# RFRxTx_2550_a.net
KiCad netlist of a schematic drawn in EAGLE
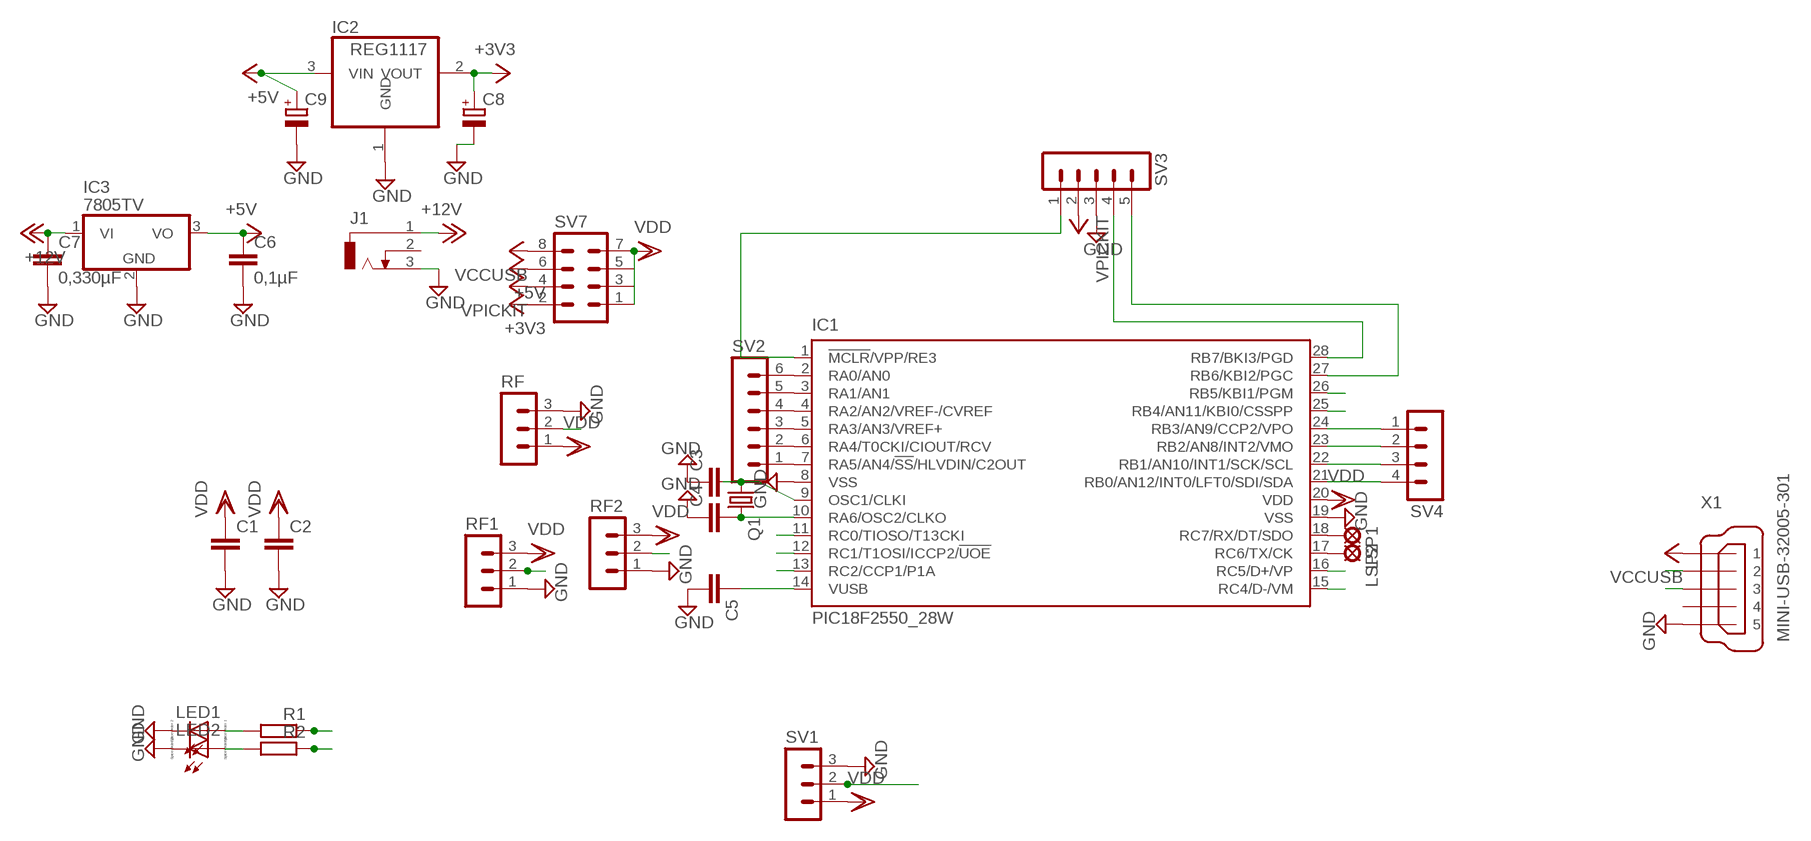
[diagram p0: schematic, sheet 1]

(export (version "E")
  (design (tool "Eeschema 10.0.6"))
  (components
    (comp (ref "C1")
      (value "C-EUC0805")
      (footprint "eagle-import:C0805")
      (libsource (lib "eagle-import") (part "C-EUC0805"))
    )
    (comp (ref "C2")
      (value "C-EUC0805")
      (footprint "eagle-import:C0805")
      (libsource (lib "eagle-import") (part "C-EUC0805"))
    )
    (comp (ref "C3")
      (value "C-EUC0805")
      (footprint "eagle-import:C0805")
      (libsource (lib "eagle-import") (part "C-EUC0805"))
    )
    (comp (ref "C4")
      (value "C-EUC0805")
      (footprint "eagle-import:C0805")
      (libsource (lib "eagle-import") (part "C-EUC0805"))
    )
    (comp (ref "C5")
      (value "C-EUC0805")
      (footprint "eagle-import:C0805")
      (libsource (lib "eagle-import") (part "C-EUC0805"))
    )
    (comp (ref "C6")
      (value "0,1µF")
      (footprint "eagle-import:C0805")
      (libsource (lib "eagle-import") (part "resistor_C-EUC0805"))
    )
    (comp (ref "C7")
      (value "0,330µF")
      (footprint "eagle-import:C0805")
      (libsource (lib "eagle-import") (part "resistor_C-EUC0805"))
    )
    (comp (ref "C8")
      (value "CPOL-EU153CLV-0405")
      (footprint "eagle-import:153CLV-0405")
      (libsource (lib "eagle-import") (part "CPOL-EU153CLV-0405"))
    )
    (comp (ref "C9")
      (value "CPOL-EU153CLV-0405")
      (footprint "eagle-import:153CLV-0405")
      (libsource (lib "eagle-import") (part "CPOL-EU153CLV-0405"))
    )
    (comp (ref "IC1")
      (value "PIC18F2550_28W")
      (footprint "eagle-import:SO28W")
      (fields (field (name "MF") "MICROCHIP") (field (name "MPN") "PIC18F2550-I/SO"))
      (libsource (lib "eagle-import") (part "PIC18F2_28W550"))
    )
    (comp (ref "IC2")
      (value "REG1117")
      (footprint "eagle-import:SOT223")
      (libsource (lib "eagle-import") (part "REG1117"))
    )
    (comp (ref "IC3")
      (value "7805TV")
      (footprint "eagle-import:TO220V")
      (libsource (lib "eagle-import") (part "78TV05"))
    )
    (comp (ref "J1")
      (value "DCJ0303")
      (footprint "eagle-import:DCJ0303")
      (libsource (lib "eagle-import") (part "DCJ0303"))
    )
    (comp (ref "LED1")
      (value "LED_ESML0603")
      (footprint "eagle-import:LED_SML0603")
      (libsource (lib "eagle-import") (part "LED_ESML0603"))
    )
    (comp (ref "LED2")
      (value "LED_ESML0603")
      (footprint "eagle-import:LED_SML0603")
      (libsource (lib "eagle-import") (part "LED_ESML0603"))
    )
    (comp (ref "LSP1")
      (value "LSP10")
      (footprint "eagle-import:LSP10")
      (libsource (lib "eagle-import") (part "LSP10"))
    )
    (comp (ref "LSP2")
      (value "LSP10")
      (footprint "eagle-import:LSP10")
      (libsource (lib "eagle-import") (part "LSP10"))
    )
    (comp (ref "Q1")
      (value "CRYSTALSM49")
      (footprint "eagle-import:SM49")
      (libsource (lib "eagle-import") (part "CRYSTALSM49"))
    )
    (comp (ref "R1")
      (value "R-EU_R0805")
      (footprint "eagle-import:R0805")
      (libsource (lib "eagle-import") (part "R-EU_R0805"))
    )
    (comp (ref "R2")
      (value "R-EU_R0805")
      (footprint "eagle-import:R0805")
      (libsource (lib "eagle-import") (part "R-EU_R0805"))
    )
    (comp (ref "RF")
      (value "MA03-1")
      (footprint "eagle-import:MA03-1")
      (libsource (lib "eagle-import") (part "MA03-1"))
    )
    (comp (ref "RF1")
      (value "MA03-1")
      (footprint "eagle-import:MA03-1")
      (libsource (lib "eagle-import") (part "MA03-1"))
    )
    (comp (ref "RF2")
      (value "MA03-1")
      (footprint "eagle-import:MA03-1")
      (libsource (lib "eagle-import") (part "MA03-1"))
    )
    (comp (ref "SV1")
      (value "MA03-1")
      (footprint "eagle-import:MA03-1")
      (libsource (lib "eagle-import") (part "MA03-1"))
    )
    (comp (ref "SV2")
      (value "MA06-1")
      (footprint "eagle-import:MA06-1")
      (libsource (lib "eagle-import") (part "MA06-1"))
    )
    (comp (ref "SV3")
      (value "MA05-1")
      (footprint "eagle-import:MA05-1")
      (libsource (lib "eagle-import") (part "MA05-1"))
    )
    (comp (ref "SV4")
      (value "MA04-1")
      (footprint "eagle-import:MA04-1")
      (libsource (lib "eagle-import") (part "MA04-1"))
    )
    (comp (ref "SV7")
      (value "MA04-2")
      (footprint "eagle-import:MA04-2")
      (libsource (lib "eagle-import") (part "MA04-2"))
    )
    (comp (ref "X1")
      (value "MINI-USB-32005-301")
      (footprint "eagle-import:32005-301")
      (libsource (lib "eagle-import") (part "MINI-USB-32005-301"))
    )
  )
  (nets
    (net (code "1") (name "+3V3") (class "Default")
      (node (ref "C8") (pin "+") (pinfunction "+_+") (pintype "passive"))
      (node (ref "IC2") (pin "2") (pinfunction "VOUT_2") (pintype "output"))
      (node (ref "SV7") (pin "2") (pinfunction "2_2") (pintype "passive"))
    )
    (net (code "2") (name "+5V") (class "Default")
      (node (ref "C6") (pin "1") (pinfunction "1_1") (pintype "passive"))
      (node (ref "C9") (pin "+") (pinfunction "+_+") (pintype "passive"))
      (node (ref "IC2") (pin "3") (pinfunction "VIN_3") (pintype "input"))
      (node (ref "IC3") (pin "3") (pinfunction "VO_3") (pintype "passive"))
      (node (ref "SV7") (pin "6") (pinfunction "6_6") (pintype "passive"))
    )
    (net (code "3") (name "+12V") (class "Default")
      (node (ref "C7") (pin "1") (pinfunction "1_1") (pintype "passive"))
      (node (ref "IC3") (pin "1") (pinfunction "VI_1") (pintype "input"))
      (node (ref "J1") (pin "1") (pinfunction "1_1") (pintype "passive"))
    )
    (net (code "4") (name "/CCP2") (class "Default")
      (node (ref "IC1") (pin "24") (pinfunction "RB3/AN9/CCP2/VPO_24") (pintype "bidirectional"))
      (node (ref "SV1") (pin "2") (pinfunction "2_2") (pintype "passive"))
      (node (ref "SV4") (pin "1") (pinfunction "1_1") (pintype "passive"))
    )
    (net (code "5") (name "/D+") (class "Default")
      (node (ref "IC1") (pin "16") (pinfunction "RC5/D+/VP_16") (pintype "bidirectional"))
      (node (ref "X1") (pin "3") (pinfunction "3_3") (pintype "passive"))
    )
    (net (code "6") (name "/D-") (class "Default")
      (node (ref "IC1") (pin "15") (pinfunction "RC4/D-/VM_15") (pintype "bidirectional"))
      (node (ref "X1") (pin "2") (pinfunction "2_2") (pintype "passive"))
    )
    (net (code "7") (name "/IR") (class "Default")
      (node (ref "IC1") (pin "13") (pinfunction "RC2/CCP1/P1A_13") (pintype "bidirectional"))
      (node (ref "RF1") (pin "2") (pinfunction "2_2") (pintype "passive"))
    )
    (net (code "8") (name "/RB4") (class "Default")
      (node (ref "IC1") (pin "25") (pinfunction "RB4/AN11/KBI0/CSSPP_25") (pintype "bidirectional"))
      (node (ref "R2") (pin "1") (pinfunction "1_1") (pintype "passive"))
    )
    (net (code "9") (name "/RB5") (class "Default")
      (node (ref "IC1") (pin "26") (pinfunction "RB5/KBI1/PGM_26") (pintype "bidirectional"))
      (node (ref "R1") (pin "1") (pinfunction "1_1") (pintype "passive"))
    )
    (net (code "10") (name "/RC0") (class "Default")
      (node (ref "IC1") (pin "11") (pinfunction "RC0/TIOSO/T13CKI_11") (pintype "bidirectional"))
      (node (ref "RF2") (pin "2") (pinfunction "2_2") (pintype "passive"))
    )
    (net (code "11") (name "/RF") (class "Default")
      (node (ref "IC1") (pin "12") (pinfunction "RC1/T1OSI/ICCP2/~{UOE}_12") (pintype "bidirectional"))
      (node (ref "RF") (pin "2") (pinfunction "2_2") (pintype "passive"))
    )
    (net (code "12") (name "GND") (class "Default")
      (node (ref "C1") (pin "2") (pinfunction "2_2") (pintype "passive"))
      (node (ref "C2") (pin "2") (pinfunction "2_2") (pintype "passive"))
      (node (ref "C3") (pin "1") (pinfunction "1_1") (pintype "passive"))
      (node (ref "C4") (pin "1") (pinfunction "1_1") (pintype "passive"))
      (node (ref "C5") (pin "2") (pinfunction "2_2") (pintype "passive"))
      (node (ref "C6") (pin "2") (pinfunction "2_2") (pintype "passive"))
      (node (ref "C7") (pin "2") (pinfunction "2_2") (pintype "passive"))
      (node (ref "C8") (pin "-") (pinfunction "-_-") (pintype "passive"))
      (node (ref "C9") (pin "-") (pinfunction "-_-") (pintype "passive"))
      (node (ref "IC1") (pin "19") (pinfunction "VSS_19") (pintype "power_in"))
      (node (ref "IC1") (pin "8") (pinfunction "VSS_8") (pintype "power_in"))
      (node (ref "IC2") (pin "1") (pinfunction "GND_1") (pintype "power_in"))
      (node (ref "IC3") (pin "2") (pinfunction "GND_2") (pintype "passive"))
      (node (ref "J1") (pin "3") (pinfunction "3_3") (pintype "passive"))
      (node (ref "LED1") (pin "C") (pinfunction "C_C") (pintype "passive"))
      (node (ref "LED2") (pin "C") (pinfunction "C_C") (pintype "passive"))
      (node (ref "RF") (pin "3") (pinfunction "3_3") (pintype "passive"))
      (node (ref "RF1") (pin "1") (pinfunction "1_1") (pintype "passive"))
      (node (ref "RF2") (pin "1") (pinfunction "1_1") (pintype "passive"))
      (node (ref "SV1") (pin "3") (pinfunction "3_3") (pintype "passive"))
      (node (ref "SV3") (pin "3") (pinfunction "3_3") (pintype "passive"))
      (node (ref "X1") (pin "5") (pinfunction "5_5") (pintype "passive"))
    )
    (net (code "13") (name "Net-(IC1-OSC1{slash}CLKI)") (class "Default")
      (node (ref "C3") (pin "2") (pinfunction "2_2") (pintype "passive"))
      (node (ref "IC1") (pin "9") (pinfunction "OSC1/CLKI_9") (pintype "input"))
      (node (ref "Q1") (pin "1") (pinfunction "1_1") (pintype "passive"))
    )
    (net (code "14") (name "Net-(IC1-RA0{slash}AN0)") (class "Default")
      (node (ref "IC1") (pin "2") (pinfunction "RA0/AN0_2") (pintype "bidirectional"))
      (node (ref "SV2") (pin "6") (pinfunction "6_6") (pintype "passive"))
    )
    (net (code "15") (name "Net-(IC1-RA1{slash}AN1)") (class "Default")
      (node (ref "IC1") (pin "3") (pinfunction "RA1/AN1_3") (pintype "bidirectional"))
      (node (ref "SV2") (pin "5") (pinfunction "5_5") (pintype "passive"))
    )
    (net (code "16") (name "Net-(IC1-RA2{slash}AN2{slash}VREF-{slash}CVREF)") (class "Default")
      (node (ref "IC1") (pin "4") (pinfunction "RA2/AN2/VREF-/CVREF_4") (pintype "bidirectional"))
      (node (ref "SV2") (pin "4") (pinfunction "4_4") (pintype "passive"))
    )
    (net (code "17") (name "Net-(IC1-RA3{slash}AN3{slash}VREF+)") (class "Default")
      (node (ref "IC1") (pin "5") (pinfunction "RA3/AN3/VREF+_5") (pintype "bidirectional"))
      (node (ref "SV2") (pin "3") (pinfunction "3_3") (pintype "passive"))
    )
    (net (code "18") (name "Net-(IC1-RA4{slash}T0CKI{slash}CIOUT{slash}RCV)") (class "Default")
      (node (ref "IC1") (pin "6") (pinfunction "RA4/T0CKI/CIOUT/RCV_6") (pintype "bidirectional"))
      (node (ref "SV2") (pin "2") (pinfunction "2_2") (pintype "passive"))
    )
    (net (code "19") (name "Net-(IC1-RA5{slash}AN4{slash}~{SS}{slash}HLVDIN{slash}C2OUT)") (class "Default")
      (node (ref "IC1") (pin "7") (pinfunction "RA5/AN4/~{SS}/HLVDIN/C2OUT_7") (pintype "bidirectional"))
      (node (ref "SV2") (pin "1") (pinfunction "1_1") (pintype "passive"))
    )
    (net (code "20") (name "Net-(IC1-RA6{slash}OSC2{slash}CLKO)") (class "Default")
      (node (ref "C4") (pin "2") (pinfunction "2_2") (pintype "passive"))
      (node (ref "IC1") (pin "10") (pinfunction "RA6/OSC2/CLKO_10") (pintype "output"))
      (node (ref "Q1") (pin "2") (pinfunction "2_2") (pintype "passive"))
    )
    (net (code "21") (name "Net-(IC1-RB0{slash}AN12{slash}INT0{slash}LFT0{slash}SDI{slash}SDA)") (class "Default")
      (node (ref "IC1") (pin "21") (pinfunction "RB0/AN12/INT0/LFT0/SDI/SDA_21") (pintype "bidirectional"))
      (node (ref "SV4") (pin "4") (pinfunction "4_4") (pintype "passive"))
    )
    (net (code "22") (name "Net-(IC1-RB1{slash}AN10{slash}INT1{slash}SCK{slash}SCL)") (class "Default")
      (node (ref "IC1") (pin "22") (pinfunction "RB1/AN10/INT1/SCK/SCL_22") (pintype "bidirectional"))
      (node (ref "SV4") (pin "3") (pinfunction "3_3") (pintype "passive"))
    )
    (net (code "23") (name "Net-(IC1-RB2{slash}AN8{slash}INT2{slash}VMO)") (class "Default")
      (node (ref "IC1") (pin "23") (pinfunction "RB2/AN8/INT2/VMO_23") (pintype "bidirectional"))
      (node (ref "SV4") (pin "2") (pinfunction "2_2") (pintype "passive"))
    )
    (net (code "24") (name "Net-(IC1-RB6{slash}KBI2{slash}PGC)") (class "Default")
      (node (ref "IC1") (pin "27") (pinfunction "RB6/KBI2/PGC_27") (pintype "bidirectional"))
      (node (ref "SV3") (pin "5") (pinfunction "5_5") (pintype "passive"))
    )
    (net (code "25") (name "Net-(IC1-RB7{slash}BKI3{slash}PGD)") (class "Default")
      (node (ref "IC1") (pin "28") (pinfunction "RB7/BKI3/PGD_28") (pintype "bidirectional"))
      (node (ref "SV3") (pin "4") (pinfunction "4_4") (pintype "passive"))
    )
    (net (code "26") (name "Net-(IC1-RC6{slash}TX{slash}CK)") (class "Default")
      (node (ref "IC1") (pin "17") (pinfunction "RC6/TX/CK_17") (pintype "bidirectional"))
      (node (ref "LSP2") (pin "MP") (pinfunction "MP_MP") (pintype "passive"))
    )
    (net (code "27") (name "Net-(IC1-RC7{slash}RX{slash}DT{slash}SDO)") (class "Default")
      (node (ref "IC1") (pin "18") (pinfunction "RC7/RX/DT/SDO_18") (pintype "bidirectional"))
      (node (ref "LSP1") (pin "MP") (pinfunction "MP_MP") (pintype "passive"))
    )
    (net (code "28") (name "Net-(IC1-VUSB)") (class "Default")
      (node (ref "C5") (pin "1") (pinfunction "1_1") (pintype "passive"))
      (node (ref "IC1") (pin "14") (pinfunction "VUSB_14") (pintype "bidirectional"))
    )
    (net (code "29") (name "Net-(IC1-~{MCLR}{slash}VPP{slash}RE3)") (class "Default")
      (node (ref "IC1") (pin "1") (pinfunction "~{MCLR}/VPP/RE3_1") (pintype "input"))
      (node (ref "SV3") (pin "1") (pinfunction "1_1") (pintype "passive"))
    )
    (net (code "30") (name "Net-(LED1-PadA)") (class "Default")
      (node (ref "LED1") (pin "A") (pinfunction "A_A") (pintype "passive"))
      (node (ref "R1") (pin "2") (pinfunction "2_2") (pintype "passive"))
    )
    (net (code "31") (name "Net-(LED2-PadA)") (class "Default")
      (node (ref "LED2") (pin "A") (pinfunction "A_A") (pintype "passive"))
      (node (ref "R2") (pin "2") (pinfunction "2_2") (pintype "passive"))
    )
    (net (code "32") (name "VCCUSB") (class "Default")
      (node (ref "SV7") (pin "8") (pinfunction "8_8") (pintype "passive"))
      (node (ref "X1") (pin "1") (pinfunction "1_1") (pintype "passive"))
    )
    (net (code "33") (name "VDD") (class "Default")
      (node (ref "C1") (pin "1") (pinfunction "1_1") (pintype "passive"))
      (node (ref "C2") (pin "1") (pinfunction "1_1") (pintype "passive"))
      (node (ref "IC1") (pin "20") (pinfunction "VDD_20") (pintype "power_in"))
      (node (ref "RF") (pin "1") (pinfunction "1_1") (pintype "passive"))
      (node (ref "RF1") (pin "3") (pinfunction "3_3") (pintype "passive"))
      (node (ref "RF2") (pin "3") (pinfunction "3_3") (pintype "passive"))
      (node (ref "SV1") (pin "1") (pinfunction "1_1") (pintype "passive"))
      (node (ref "SV7") (pin "1") (pinfunction "1_1") (pintype "passive"))
      (node (ref "SV7") (pin "3") (pinfunction "3_3") (pintype "passive"))
      (node (ref "SV7") (pin "5") (pinfunction "5_5") (pintype "passive"))
      (node (ref "SV7") (pin "7") (pinfunction "7_7") (pintype "passive"))
    )
    (net (code "34") (name "VPICKIT") (class "Default")
      (node (ref "SV3") (pin "2") (pinfunction "2_2") (pintype "passive"))
      (node (ref "SV7") (pin "4") (pinfunction "4_4") (pintype "passive"))
    )
    (net (code "35") (name "unconnected-(J1-Pad2)") (class "Default")
      (node (ref "J1") (pin "2") (pinfunction "2_2") (pintype "passive"))
    )
    (net (code "36") (name "unconnected-(X1-Pad4)") (class "Default")
      (node (ref "X1") (pin "4") (pinfunction "4_4") (pintype "passive"))
    )
  )
)
